# wifi_shield.net
KiCad netlist of a schematic drawn in EAGLE
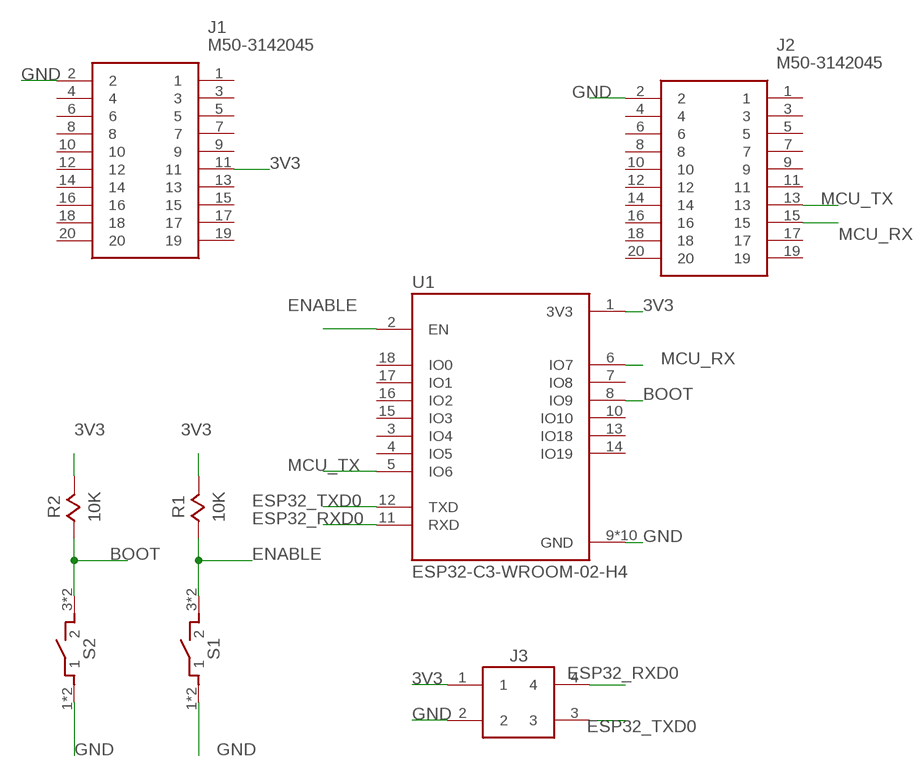
[diagram p0: schematic, sheet 1]

(export (version "E")
  (design (tool "Eeschema 10.0.6"))
  (components
    (comp (ref "J1")
      (value "M50-3142045")
      (footprint "eagle-import:M503142045")
      (fields (field (name "MOUSER_PART_NUMBER") "855-M50-3142045"))
      (libsource (lib "eagle-import") (part "M50-3142045"))
    )
    (comp (ref "J2")
      (value "M50-3142045")
      (footprint "eagle-import:M503142045")
      (fields (field (name "MOUSER_PART_NUMBER") "855-M50-3142045"))
      (libsource (lib "eagle-import") (part "M50-3142045"))
    )
    (comp (ref "J3")
      (value "MALE_HEADER_4X1")
      (footprint "eagle-import:4X1_HEADER")
      (libsource (lib "eagle-import") (part "MALE_HEADER_4X1"))
    )
    (comp (ref "R1")
      (value "10K")
      (footprint "eagle-import:0805")
      (libsource (lib "eagle-import") (part "RESISTOR"))
    )
    (comp (ref "R2")
      (value "10K")
      (footprint "eagle-import:0805")
      (libsource (lib "eagle-import") (part "RESISTOR"))
    )
    (comp (ref "S1")
      (value "TACTILE-SWITCH")
      (footprint "eagle-import:TACTILE-SWITCH")
      (libsource (lib "eagle-import") (part "TACTILE-SWITCH"))
    )
    (comp (ref "S2")
      (value "TACTILE-SWITCH")
      (footprint "eagle-import:TACTILE-SWITCH")
      (libsource (lib "eagle-import") (part "TACTILE-SWITCH"))
    )
    (comp (ref "U1")
      (value "ESP32-C3-WROOM-02-H4")
      (footprint "eagle-import:MODULE_ESP32-C3-WROOM-02-H4")
      (fields (field (name "MANUFACTURER") "Espressif"))
      (libsource (lib "eagle-import") (part "ESP32-C3-WROOM-02-H4"))
    )
  )
  (nets
    (net (code "1") (name "/3V3") (class "Default")
      (node (ref "J1") (pin "11") (pinfunction "11_11") (pintype "bidirectional"))
      (node (ref "J3") (pin "1") (pinfunction "1_1") (pintype "bidirectional"))
      (node (ref "R1") (pin "2") (pinfunction "2_2") (pintype "bidirectional"))
      (node (ref "R2") (pin "2") (pinfunction "2_2") (pintype "bidirectional"))
      (node (ref "U1") (pin "1") (pinfunction "3V3_1") (pintype "power_in"))
    )
    (net (code "2") (name "/BOOT") (class "Default")
      (node (ref "R2") (pin "1") (pinfunction "1_1") (pintype "bidirectional"))
      (node (ref "S2") (pin "3") (pinfunction "2_3") (pintype "bidirectional"))
      (node (ref "S2") (pin "4") (pinfunction "2_4") (pintype "bidirectional"))
      (node (ref "U1") (pin "8") (pinfunction "IO9_8") (pintype "bidirectional"))
    )
    (net (code "3") (name "/ENABLE") (class "Default")
      (node (ref "R1") (pin "1") (pinfunction "1_1") (pintype "bidirectional"))
      (node (ref "S1") (pin "3") (pinfunction "2_3") (pintype "bidirectional"))
      (node (ref "S1") (pin "4") (pinfunction "2_4") (pintype "bidirectional"))
      (node (ref "U1") (pin "2") (pinfunction "EN_2") (pintype "input"))
    )
    (net (code "4") (name "/ESP32_RXD0") (class "Default")
      (node (ref "J3") (pin "4") (pinfunction "4_4") (pintype "bidirectional"))
      (node (ref "U1") (pin "11") (pinfunction "RXD_11") (pintype "bidirectional"))
    )
    (net (code "5") (name "/ESP32_TXD0") (class "Default")
      (node (ref "J3") (pin "3") (pinfunction "3_3") (pintype "bidirectional"))
      (node (ref "U1") (pin "12") (pinfunction "TXD_12") (pintype "bidirectional"))
    )
    (net (code "6") (name "/GND") (class "Default")
      (node (ref "J1") (pin "2") (pinfunction "2_2") (pintype "bidirectional"))
      (node (ref "J2") (pin "2") (pinfunction "2_2") (pintype "bidirectional"))
      (node (ref "J3") (pin "2") (pinfunction "2_2") (pintype "bidirectional"))
      (node (ref "S1") (pin "1") (pinfunction "1_1") (pintype "bidirectional"))
      (node (ref "S1") (pin "2") (pinfunction "1_2") (pintype "bidirectional"))
      (node (ref "S2") (pin "1") (pinfunction "1_1") (pintype "bidirectional"))
      (node (ref "S2") (pin "2") (pinfunction "1_2") (pintype "bidirectional"))
      (node (ref "U1") (pin "19") (pinfunction "GND_19") (pintype "power_in"))
      (node (ref "U1") (pin "20") (pinfunction "GND_20") (pintype "power_in"))
      (node (ref "U1") (pin "21") (pinfunction "GND_21") (pintype "power_in"))
      (node (ref "U1") (pin "22") (pinfunction "GND_22") (pintype "power_in"))
      (node (ref "U1") (pin "23") (pinfunction "GND_23") (pintype "power_in"))
      (node (ref "U1") (pin "24") (pinfunction "GND_24") (pintype "power_in"))
      (node (ref "U1") (pin "25") (pinfunction "GND_25") (pintype "power_in"))
      (node (ref "U1") (pin "26") (pinfunction "GND_26") (pintype "power_in"))
      (node (ref "U1") (pin "27") (pinfunction "GND_27") (pintype "power_in"))
      (node (ref "U1") (pin "9") (pinfunction "GND_9") (pintype "power_in"))
    )
    (net (code "7") (name "/MCU_RX") (class "Default")
      (node (ref "J2") (pin "15") (pinfunction "15_15") (pintype "bidirectional"))
      (node (ref "U1") (pin "6") (pinfunction "IO7_6") (pintype "bidirectional"))
    )
    (net (code "8") (name "/MCU_TX") (class "Default")
      (node (ref "J2") (pin "13") (pinfunction "13_13") (pintype "bidirectional"))
      (node (ref "U1") (pin "5") (pinfunction "IO6_5") (pintype "bidirectional"))
    )
    (net (code "9") (name "unconnected-(J1-Pad1)") (class "Default")
      (node (ref "J1") (pin "1") (pinfunction "1_1") (pintype "bidirectional"))
    )
    (net (code "10") (name "unconnected-(J1-Pad3)") (class "Default")
      (node (ref "J1") (pin "3") (pinfunction "3_3") (pintype "bidirectional"))
    )
    (net (code "11") (name "unconnected-(J1-Pad4)") (class "Default")
      (node (ref "J1") (pin "4") (pinfunction "4_4") (pintype "bidirectional"))
    )
    (net (code "12") (name "unconnected-(J1-Pad5)") (class "Default")
      (node (ref "J1") (pin "5") (pinfunction "5_5") (pintype "bidirectional"))
    )
    (net (code "13") (name "unconnected-(J1-Pad6)") (class "Default")
      (node (ref "J1") (pin "6") (pinfunction "6_6") (pintype "bidirectional"))
    )
    (net (code "14") (name "unconnected-(J1-Pad7)") (class "Default")
      (node (ref "J1") (pin "7") (pinfunction "7_7") (pintype "bidirectional"))
    )
    (net (code "15") (name "unconnected-(J1-Pad8)") (class "Default")
      (node (ref "J1") (pin "8") (pinfunction "8_8") (pintype "bidirectional"))
    )
    (net (code "16") (name "unconnected-(J1-Pad9)") (class "Default")
      (node (ref "J1") (pin "9") (pinfunction "9_9") (pintype "bidirectional"))
    )
    (net (code "17") (name "unconnected-(J1-Pad10)") (class "Default")
      (node (ref "J1") (pin "10") (pinfunction "10_10") (pintype "bidirectional"))
    )
    (net (code "18") (name "unconnected-(J1-Pad12)") (class "Default")
      (node (ref "J1") (pin "12") (pinfunction "12_12") (pintype "bidirectional"))
    )
    (net (code "19") (name "unconnected-(J1-Pad13)") (class "Default")
      (node (ref "J1") (pin "13") (pinfunction "13_13") (pintype "bidirectional"))
    )
    (net (code "20") (name "unconnected-(J1-Pad14)") (class "Default")
      (node (ref "J1") (pin "14") (pinfunction "14_14") (pintype "bidirectional"))
    )
    (net (code "21") (name "unconnected-(J1-Pad15)") (class "Default")
      (node (ref "J1") (pin "15") (pinfunction "15_15") (pintype "bidirectional"))
    )
    (net (code "22") (name "unconnected-(J1-Pad16)") (class "Default")
      (node (ref "J1") (pin "16") (pinfunction "16_16") (pintype "bidirectional"))
    )
    (net (code "23") (name "unconnected-(J1-Pad17)") (class "Default")
      (node (ref "J1") (pin "17") (pinfunction "17_17") (pintype "bidirectional"))
    )
    (net (code "24") (name "unconnected-(J1-Pad18)") (class "Default")
      (node (ref "J1") (pin "18") (pinfunction "18_18") (pintype "bidirectional"))
    )
    (net (code "25") (name "unconnected-(J1-Pad19)") (class "Default")
      (node (ref "J1") (pin "19") (pinfunction "19_19") (pintype "bidirectional"))
    )
    (net (code "26") (name "unconnected-(J1-Pad20)") (class "Default")
      (node (ref "J1") (pin "20") (pinfunction "20_20") (pintype "bidirectional"))
    )
    (net (code "27") (name "unconnected-(J2-Pad1)") (class "Default")
      (node (ref "J2") (pin "1") (pinfunction "1_1") (pintype "bidirectional"))
    )
    (net (code "28") (name "unconnected-(J2-Pad3)") (class "Default")
      (node (ref "J2") (pin "3") (pinfunction "3_3") (pintype "bidirectional"))
    )
    (net (code "29") (name "unconnected-(J2-Pad4)") (class "Default")
      (node (ref "J2") (pin "4") (pinfunction "4_4") (pintype "bidirectional"))
    )
    (net (code "30") (name "unconnected-(J2-Pad5)") (class "Default")
      (node (ref "J2") (pin "5") (pinfunction "5_5") (pintype "bidirectional"))
    )
    (net (code "31") (name "unconnected-(J2-Pad6)") (class "Default")
      (node (ref "J2") (pin "6") (pinfunction "6_6") (pintype "bidirectional"))
    )
    (net (code "32") (name "unconnected-(J2-Pad7)") (class "Default")
      (node (ref "J2") (pin "7") (pinfunction "7_7") (pintype "bidirectional"))
    )
    (net (code "33") (name "unconnected-(J2-Pad8)") (class "Default")
      (node (ref "J2") (pin "8") (pinfunction "8_8") (pintype "bidirectional"))
    )
    (net (code "34") (name "unconnected-(J2-Pad9)") (class "Default")
      (node (ref "J2") (pin "9") (pinfunction "9_9") (pintype "bidirectional"))
    )
    (net (code "35") (name "unconnected-(J2-Pad10)") (class "Default")
      (node (ref "J2") (pin "10") (pinfunction "10_10") (pintype "bidirectional"))
    )
    (net (code "36") (name "unconnected-(J2-Pad11)") (class "Default")
      (node (ref "J2") (pin "11") (pinfunction "11_11") (pintype "bidirectional"))
    )
    (net (code "37") (name "unconnected-(J2-Pad12)") (class "Default")
      (node (ref "J2") (pin "12") (pinfunction "12_12") (pintype "bidirectional"))
    )
    (net (code "38") (name "unconnected-(J2-Pad14)") (class "Default")
      (node (ref "J2") (pin "14") (pinfunction "14_14") (pintype "bidirectional"))
    )
    (net (code "39") (name "unconnected-(J2-Pad16)") (class "Default")
      (node (ref "J2") (pin "16") (pinfunction "16_16") (pintype "bidirectional"))
    )
    (net (code "40") (name "unconnected-(J2-Pad17)") (class "Default")
      (node (ref "J2") (pin "17") (pinfunction "17_17") (pintype "bidirectional"))
    )
    (net (code "41") (name "unconnected-(J2-Pad18)") (class "Default")
      (node (ref "J2") (pin "18") (pinfunction "18_18") (pintype "bidirectional"))
    )
    (net (code "42") (name "unconnected-(J2-Pad19)") (class "Default")
      (node (ref "J2") (pin "19") (pinfunction "19_19") (pintype "bidirectional"))
    )
    (net (code "43") (name "unconnected-(J2-Pad20)") (class "Default")
      (node (ref "J2") (pin "20") (pinfunction "20_20") (pintype "bidirectional"))
    )
    (net (code "44") (name "unconnected-(U1-IO0-Pad18)") (class "Default")
      (node (ref "U1") (pin "18") (pinfunction "IO0_18") (pintype "bidirectional"))
    )
    (net (code "45") (name "unconnected-(U1-IO1-Pad17)") (class "Default")
      (node (ref "U1") (pin "17") (pinfunction "IO1_17") (pintype "bidirectional"))
    )
    (net (code "46") (name "unconnected-(U1-IO2-Pad16)") (class "Default")
      (node (ref "U1") (pin "16") (pinfunction "IO2_16") (pintype "bidirectional"))
    )
    (net (code "47") (name "unconnected-(U1-IO3-Pad15)") (class "Default")
      (node (ref "U1") (pin "15") (pinfunction "IO3_15") (pintype "bidirectional"))
    )
    (net (code "48") (name "unconnected-(U1-IO4-Pad3)") (class "Default")
      (node (ref "U1") (pin "3") (pinfunction "IO4_3") (pintype "bidirectional"))
    )
    (net (code "49") (name "unconnected-(U1-IO5-Pad4)") (class "Default")
      (node (ref "U1") (pin "4") (pinfunction "IO5_4") (pintype "bidirectional"))
    )
    (net (code "50") (name "unconnected-(U1-IO8-Pad7)") (class "Default")
      (node (ref "U1") (pin "7") (pinfunction "IO8_7") (pintype "bidirectional"))
    )
    (net (code "51") (name "unconnected-(U1-IO10-Pad10)") (class "Default")
      (node (ref "U1") (pin "10") (pinfunction "IO10_10") (pintype "bidirectional"))
    )
    (net (code "52") (name "unconnected-(U1-IO18-Pad13)") (class "Default")
      (node (ref "U1") (pin "13") (pinfunction "IO18_13") (pintype "bidirectional"))
    )
    (net (code "53") (name "unconnected-(U1-IO19-Pad14)") (class "Default")
      (node (ref "U1") (pin "14") (pinfunction "IO19_14") (pintype "bidirectional"))
    )
  )
)
